# Interconnect.net
KiCad netlist of a schematic drawn in Altium Designer
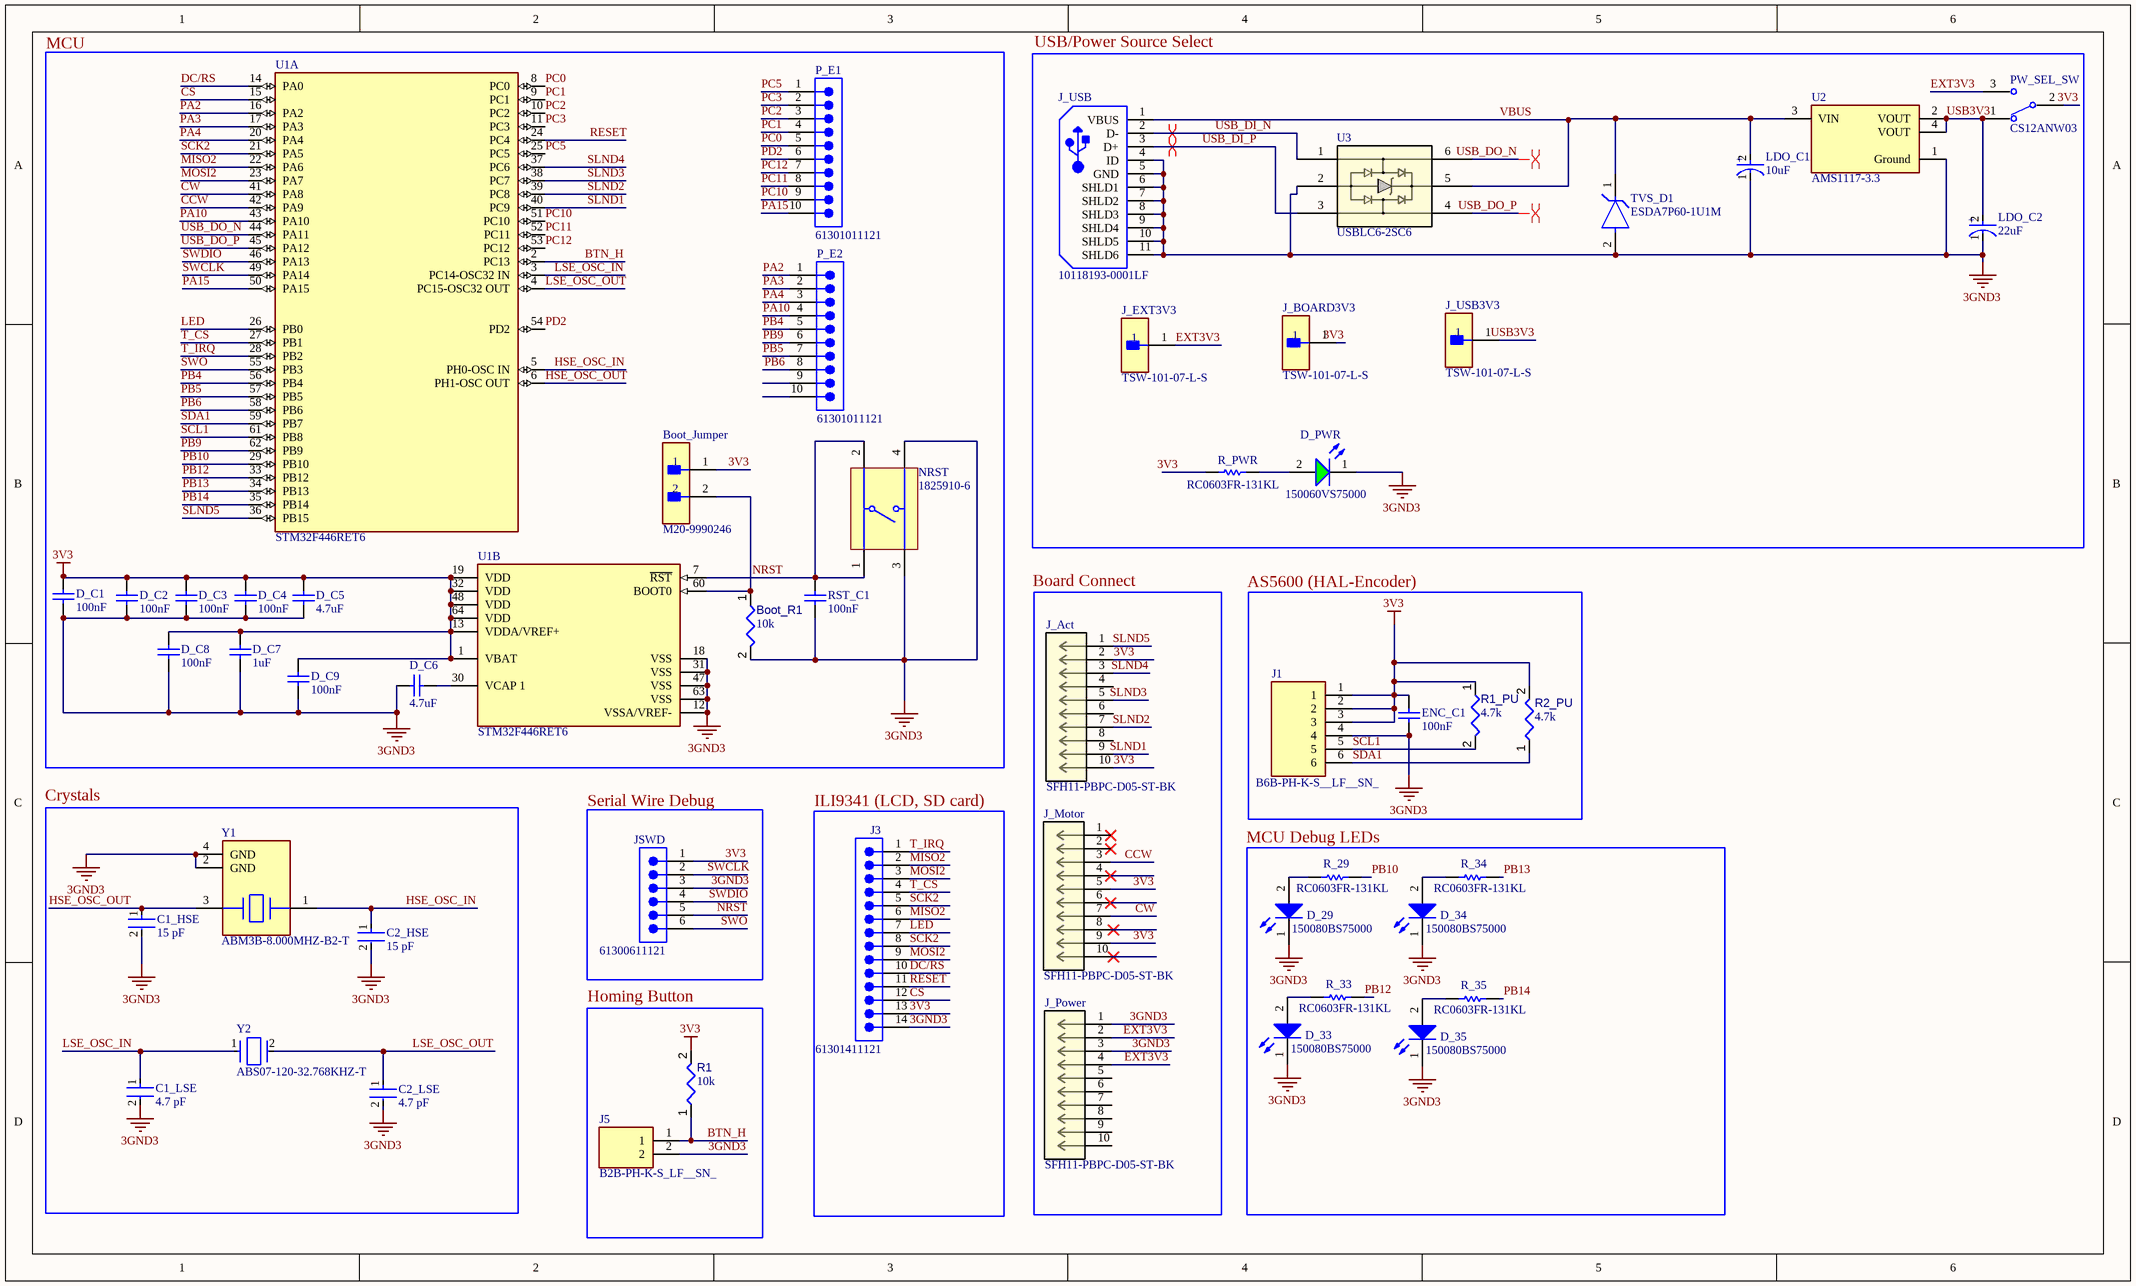
[diagram p0: Interconnect.SchDoc]

(export (version "E")
  (design (tool "Eeschema 10.0.6"))
  (components
    (comp (ref "Boot_Jumper")
      (value "M20-9990246")
      (footprint "FP-M20-9990246-MFG")
      (description "CONN HEADER VERT 2POS 2.54MM")
      (fields
        (field (name "OCTOPART") "https://octopart.com/m20-9990246-harwin-2590635")
        (field (name "MANUFACTURER") "Harwin")
      )
      (libsource (lib "Altium Content Vault") (part "3bc925449376181038e59eaffc5286c"))
    )
    (comp (ref "Boot_R1")
      (value "10k")
      (footprint "RESC1608X55X25ML10T15")
      (description "Chip Resistor, 10 KOhm, +/- 1%, 01 W, -55 to 155 degC, 0603 (1608 Metric)")
      (fields (field (name "POWER") "100mW") (field (name "TOLERANCE") "1%"))
      (libsource (lib "Chathil Rajamanthree") (part "RES-2"))
    )
    (comp (ref "C1_HSE")
      (value "15 pF")
      (footprint "FP-GJM155-0_05-MFG")
      (description "Multi-Layer Ceramic Capacitor 15pF C0G  ±2% 0402 Paper T/R")
      (fields (field (name "TOLERANCE") "2%"))
      (libsource (lib "Altium Content Vault") (part "02cd4be3c70576c341d710602a673aa"))
    )
    (comp (ref "C1_LSE")
      (value "4.7 pF")
      (footprint "FP-GJM155-0_05-MFG")
      (description "Multi-Layer Ceramic Capacitor 15pF C0G  ±2% 0402 Paper T/R")
      (fields (field (name "TOLERANCE") "2%"))
      (libsource (lib "Altium Content Vault") (part "02cd4be3c70576c341d710602a673aa"))
    )
    (comp (ref "C2_HSE")
      (value "15 pF")
      (footprint "FP-GJM155-0_05-MFG")
      (description "Multi-Layer Ceramic Capacitor 15pF C0G  ±2% 0402 Paper T/R")
      (fields (field (name "TOLERANCE") "2%"))
      (libsource (lib "Altium Content Vault") (part "02cd4be3c70576c341d710602a673aa"))
    )
    (comp (ref "C2_LSE")
      (value "4.7 pF")
      (footprint "FP-GJM155-0_05-MFG")
      (description "Multi-Layer Ceramic Capacitor 15pF C0G  ±2% 0402 Paper T/R")
      (fields (field (name "TOLERANCE") "2%"))
      (libsource (lib "Altium Content Vault") (part "02cd4be3c70576c341d710602a673aa"))
    )
    (comp (ref "D_29")
      (value "150080BS75000")
      (footprint "WL-SMCW_0805_150080xx75000")
      (description "Led, Blue, 470 Nm, 3.2 V, 30 Ma, 145 Mcd Rohs Compliant: Yes")
      (libsource (lib "Altium Content Vault") (part "LED_Blue_2A-1K"))
    )
    (comp (ref "D_33")
      (value "150080BS75000")
      (footprint "WL-SMCW_0805_150080xx75000")
      (description "Led, Blue, 470 Nm, 3.2 V, 30 Ma, 145 Mcd Rohs Compliant: Yes")
      (libsource (lib "Altium Content Vault") (part "LED_Blue_2A-1K"))
    )
    (comp (ref "D_34")
      (value "150080BS75000")
      (footprint "WL-SMCW_0805_150080xx75000")
      (description "Led, Blue, 470 Nm, 3.2 V, 30 Ma, 145 Mcd Rohs Compliant: Yes")
      (libsource (lib "Altium Content Vault") (part "LED_Blue_2A-1K"))
    )
    (comp (ref "D_35")
      (value "150080BS75000")
      (footprint "WL-SMCW_0805_150080xx75000")
      (description "Led, Blue, 470 Nm, 3.2 V, 30 Ma, 145 Mcd Rohs Compliant: Yes")
      (libsource (lib "Altium Content Vault") (part "LED_Blue_2A-1K"))
    )
    (comp (ref "D_C1")
      (value "100nF")
      (footprint "CAPC1608X90X35NL15T15")
      (fields (field (name "PART NUMBER") "C0603C104K4RAC7013") (field (name "MANUFACTURER") "Kemet"))
      (libsource (lib "Altium Content Vault") (part "CAP"))
    )
    (comp (ref "D_C2")
      (value "100nF")
      (footprint "CAPC1608X90X35NL15T15")
      (fields (field (name "PART NUMBER") "C0603C104K4RAC7013") (field (name "MANUFACTURER") "Kemet"))
      (libsource (lib "Altium Content Vault") (part "CAP"))
    )
    (comp (ref "D_C3")
      (value "100nF")
      (footprint "CAPC1608X90X35NL15T15")
      (fields (field (name "PART NUMBER") "C0603C104K4RAC7013") (field (name "MANUFACTURER") "Kemet"))
      (libsource (lib "Altium Content Vault") (part "CAP"))
    )
    (comp (ref "D_C4")
      (value "100nF")
      (footprint "CAPC1608X90X35NL15T15")
      (fields (field (name "PART NUMBER") "C0603C104K4RAC7013") (field (name "MANUFACTURER") "Kemet"))
      (libsource (lib "Altium Content Vault") (part "CAP"))
    )
    (comp (ref "D_C5")
      (value "4.7uF")
      (footprint "CAPC1608X90X35NL15T15")
      (fields (field (name "PART NUMBER") "C0603C104K4RAC7013") (field (name "MANUFACTURER") "Kemet"))
      (libsource (lib "Altium Content Vault") (part "CAP"))
    )
    (comp (ref "D_C6")
      (value "4.7uF")
      (footprint "CAPC1608X90X35NL15T15")
      (fields (field (name "PART NUMBER") "C0603C104K4RAC7013") (field (name "MANUFACTURER") "Kemet"))
      (libsource (lib "Altium Content Vault") (part "CAP"))
    )
    (comp (ref "D_C7")
      (value "1uF")
      (footprint "CAPC1608X90X35NL15T15")
      (fields (field (name "PART NUMBER") "C0603C104K4RAC7013") (field (name "MANUFACTURER") "Kemet"))
      (libsource (lib "Altium Content Vault") (part "CAP"))
    )
    (comp (ref "D_C8")
      (value "100nF")
      (footprint "CAPC1608X90X35NL15T15")
      (fields (field (name "PART NUMBER") "C0603C104K4RAC7013") (field (name "MANUFACTURER") "Kemet"))
      (libsource (lib "Altium Content Vault") (part "CAP"))
    )
    (comp (ref "D_C9")
      (value "100nF")
      (footprint "CAPC1608X90X35NL15T15")
      (fields (field (name "PART NUMBER") "C0603C104K4RAC7013") (field (name "MANUFACTURER") "Kemet"))
      (libsource (lib "Altium Content Vault") (part "CAP"))
    )
    (comp (ref "D_PWR")
      (value "150060VS75000")
      (footprint "WL-SMCW_0603_150060xx75000")
      (description "WURTH ELEKTRONIK - 150060VS75000 - LED, Green, SMD, 0603, 30 mA, 2 V, 570 nm")
      (libsource (lib "Altium Content Vault") (part "LED_Green_2A-1K"))
    )
    (comp (ref "ENC_C1")
      (value "100nF")
      (footprint "CAPC1608X90X35NL15T15")
      (fields (field (name "PART NUMBER") "C0603C104K4RAC7013") (field (name "MANUFACTURER") "Kemet"))
      (libsource (lib "Altium Content Vault") (part "CAP"))
    )
    (comp (ref "J1")
      (value "B6B-PH-K-S__LF__SN_")
      (footprint "SamacSys:SHDR6W50P0X200_1X6_1390X450X600P")
      (description "Connector")
      (fields (field (name "MANUFACTURER_PART_NUMBER") "B6B-PH-K-S (LF)(SN)"))
      (libsource (lib "*") (part "B6B-PH-K-S__LF__SN_"))
    )
    (comp (ref "J3")
      (value "61301411121")
      (footprint "61301411121")
      (description "THT Vertical Pin Header WR-PHD, Pitch 2.54 mm, Single Row, 14 pins")
      (libsource (lib "Altium Content Vault") (part "Header_Male_1R_14P"))
    )
    (comp (ref "J5")
      (value "B2B-PH-K-S_LF__SN_")
      (footprint "SamacSys:SHDR2W50P0X200_1X2_590X450X600P")
      (description "Connector")
      (fields
        (field (name "MANUFACTURER_PART_NUMBER") "B2B-PH-K-S(LF)(SN)")
        (field (name "MOUSER PART NUMBER") "306-B2BPHKSLFSNPP")
      )
      (libsource (lib "SamacSys") (part "B2B-PH-K-S_LF__SN_"))
    )
    (comp (ref "JSWD")
      (value "61300611121")
      (footprint "61300611121")
      (description "THT Vertical Pin Header WR-PHD, Pitch 2.54 mm, Single Row, 6 pins")
      (libsource (lib "Altium Content Vault") (part "Header_Male_1R_06P"))
    )
    (comp (ref "J_Act")
      (value "SFH11-PBPC-D05-ST-BK")
      (footprint "CONN_SFH11-xxxC-D05-ST-XX_SUL")
      (description "Description")
      (fields (field (name "COPYRIGHT") "Copyright (C) 2025 Ultra Librarian. All rights reserved."))
      (libsource (lib "SFH11-PBPC-D05-ST-BK") (part "SFH11-PBPC-D05-ST-BK"))
    )
    (comp (ref "J_BOARD3V3")
      (value "TSW-101-07-L-S")
      (footprint "FP-TSW-101-07-L-S-MFG")
      (description "CONN HEADER VERT 1POS")
      (libsource (lib "Altium Content Vault") (part "dd45045ce8184df9e99e12baf3f412c"))
    )
    (comp (ref "J_EXT3V3")
      (value "TSW-101-07-L-S")
      (footprint "FP-TSW-101-07-L-S-MFG")
      (description "CONN HEADER VERT 1POS")
      (libsource (lib "Altium Content Vault") (part "dd45045ce8184df9e99e12baf3f412c"))
    )
    (comp (ref "J_Motor")
      (value "SFH11-PBPC-D05-ST-BK")
      (footprint "CONN_SFH11-xxxC-D05-ST-XX_SUL")
      (description "Description")
      (fields (field (name "COPYRIGHT") "Copyright (C) 2025 Ultra Librarian. All rights reserved."))
      (libsource (lib "SFH11-PBPC-D05-ST-BK") (part "SFH11-PBPC-D05-ST-BK"))
    )
    (comp (ref "J_Power")
      (value "SFH11-PBPC-D05-ST-BK")
      (footprint "CONN_SFH11-xxxC-D05-ST-XX_SUL")
      (description "Description")
      (fields (field (name "COPYRIGHT") "Copyright (C) 2025 Ultra Librarian. All rights reserved."))
      (libsource (lib "SFH11-PBPC-D05-ST-BK") (part "SFH11-PBPC-D05-ST-BK"))
    )
    (comp (ref "J_USB")
      (value "10118193-0001LF")
      (footprint "FCI-10118193-0001LF-5_V")
      (description "Micro USB B Type Receptacle, -55 to 85 degC, 5-Pin SMD, RoHS, Tape and Reel")
      (fields (field (name "MANUFACTURER") "FCI"))
      (libsource (lib "Altium Content Vault") (part "USB-5-6SHLD"))
    )
    (comp (ref "J_USB3V3")
      (value "TSW-101-07-L-S")
      (footprint "FP-TSW-101-07-L-S-MFG")
      (description "CONN HEADER VERT 1POS")
      (libsource (lib "Altium Content Vault") (part "dd45045ce8184df9e99e12baf3f412c"))
    )
    (comp (ref "LDO_C1")
      (value "10uF")
      (footprint "FP-TAJA-MFG")
      (description "10uF 10V  ±20% 3Ω 1206  SMD Tantalum Capacitor")
      (fields (field (name "TOLERANCE") "20%") (field (name "VOLTAGE") "10V"))
      (libsource (lib "Altium Content Vault") (part "203bc49f2ac43e59fd269a8c329ed05"))
    )
    (comp (ref "LDO_C2")
      (value "22uF")
      (footprint "FP-TAJA-MFG")
      (description "10uF 10V  ±20% 3Ω 1206  SMD Tantalum Capacitor")
      (fields (field (name "TOLERANCE") "20%") (field (name "VOLTAGE") "10V"))
      (libsource (lib "Altium Content Vault") (part "203bc49f2ac43e59fd269a8c329ed05"))
    )
    (comp (ref "NRST")
      (value "1825910-6")
      (footprint "TECO-1825910-6_V")
      (description "Tact Switch, SPST-NO, 0.05 A, -35 to 85 degC, 4-Pin THD, RoHS, Bulk")
      (fields (field (name "MANUFACTURER") "TE Connectivity"))
      (libsource (lib "Altium Content Vault") (part "SW-SPST-4_A"))
    )
    (comp (ref "PW_SEL_SW")
      (value "CS12ANW03")
      (footprint "FP-CS12ANW03-MFG")
      (description "SWITCH SLIDE SPDT 3A 125V")
      (libsource (lib "Altium Content Vault") (part "12161840acc88c497b895bf2e19a5b1"))
    )
    (comp (ref "P_E1")
      (value "61301011121")
      (footprint "61301011121")
      (description "THT Vertical Pin Header WR-PHD, Pitch 2.54 mm, Single Row, 10 pins")
      (libsource (lib "Altium Content Vault") (part "Header_Male_1R_10P"))
    )
    (comp (ref "P_E2")
      (value "61301011121")
      (footprint "61301011121")
      (description "THT Vertical Pin Header WR-PHD, Pitch 2.54 mm, Single Row, 10 pins")
      (libsource (lib "Altium Content Vault") (part "Header_Male_1R_10P"))
    )
    (comp (ref "R1")
      (value "10k")
      (footprint "RESC1608X55X25ML10T15")
      (description "Chip Resistor, 10 KOhm, +/- 1%, 01 W, -55 to 155 degC, 0603 (1608 Metric)")
      (fields (field (name "POWER") "100mW") (field (name "TOLERANCE") "1%"))
      (libsource (lib "Chathil Rajamanthree") (part "RES-2"))
    )
    (comp (ref "R1_PU")
      (value "4.7k")
      (footprint "RESC1608X55X25ML10T15")
      (description "Chip Resistor, 10 KOhm, +/- 1%, 01 W, -55 to 155 degC, 0603 (1608 Metric)")
      (fields (field (name "POWER") "100mW") (field (name "TOLERANCE") "1%"))
      (libsource (lib "Chathil Rajamanthree") (part "RES-2"))
    )
    (comp (ref "R2_PU")
      (value "4.7k")
      (footprint "RESC1608X55X25ML10T15")
      (description "Chip Resistor, 10 KOhm, +/- 1%, 01 W, -55 to 155 degC, 0603 (1608 Metric)")
      (fields (field (name "POWER") "100mW") (field (name "TOLERANCE") "1%"))
      (libsource (lib "Chathil Rajamanthree") (part "RES-2"))
    )
    (comp (ref "RST_C1")
      (value "100nF")
      (footprint "CAPC1608X90X35NL15T15")
      (fields (field (name "PART NUMBER") "C0603C104K4RAC7013") (field (name "MANUFACTURER") "Kemet"))
      (libsource (lib "Altium Content Vault") (part "CAP"))
    )
    (comp (ref "R_29")
      (value "RC0603FR-131KL")
      (footprint "RESC1608X55X25NL10T15")
      (fields (field (name "MANUFACTURER") "Yageo"))
      (libsource (lib "Altium Content Vault") (part "RES"))
    )
    (comp (ref "R_33")
      (value "RC0603FR-131KL")
      (footprint "RESC1608X55X25NL10T15")
      (fields (field (name "MANUFACTURER") "Yageo"))
      (libsource (lib "Altium Content Vault") (part "RES"))
    )
    (comp (ref "R_34")
      (value "RC0603FR-131KL")
      (footprint "RESC1608X55X25NL10T15")
      (fields (field (name "MANUFACTURER") "Yageo"))
      (libsource (lib "Altium Content Vault") (part "RES"))
    )
    (comp (ref "R_35")
      (value "RC0603FR-131KL")
      (footprint "RESC1608X55X25NL10T15")
      (fields (field (name "MANUFACTURER") "Yageo"))
      (libsource (lib "Altium Content Vault") (part "RES"))
    )
    (comp (ref "R_PWR")
      (value "RC0603FR-131KL")
      (footprint "RESC1608X55X25NL10T15")
      (fields (field (name "MANUFACTURER") "Yageo"))
      (libsource (lib "Altium Content Vault") (part "RES"))
    )
    (comp (ref "TVS_D1")
      (value "ESDA7P60-1U1M")
      (footprint "FP-1610-MFG")
      (description "TVS DIODE 5V 11.6V 1610")
      (fields
        (field (name "MANUFACTURER") "STMicroelectronics")
        (field (name "OCTOPART") "https://octopart.com/esda7p60-1u1m-stmicroelectronics-52112702")
      )
      (libsource (lib "Altium Content Vault") (part "f813f71cba58e380607f5dd3caf9714"))
    )
    (comp (ref "U1")
      (value "STM32F446RET6")
      (footprint "FP-LQFP64-5W-MFG")
      (description "IC MCU 32BIT 512KB FLASH 64LQFP")
      (fields
        (field (name "OCTOPART") "https://octopart.com/stm32f446ret6-stmicroelectronics-52642920")
        (field (name "MANUFACTURER") "ST")
      )
      (libsource (lib "Altium Content Vault") (part "ee11adc32c0ab33b933cccf4348c338"))
    )
    (comp (ref "U2")
      (value "AMS1117-3.3")
      (footprint "FP-AMS1117-IPC_C")
      (description "LDO Voltage Regulators 1A, 3.3V")
      (fields
        (field (name "OCTOPART") "https://octopart.com/ams1117-3.3-advanced+monolithic+systems-25899300")
        (field (name "MANUFACTURER") "Advanced Monolithic Systems")
      )
      (libsource (lib "Altium Content Vault") (part "8bdbb5f8e77002000e30dd2845d0354"))
    )
    (comp (ref "U3")
      (value "USBLC6-2SC6")
      (footprint "SOT23-6L_STM")
      (description "ESD Protection for USB 2.0 High Speed")
      (fields (field (name "COPYRIGHT") "Copyright (C) 2025 Ultra Librarian. All rights reserved."))
      (libsource (lib "USBLC6-2SC6") (part "USBLC6-2SC6"))
    )
    (comp (ref "Y1")
      (value "ABM3B-8.000MHZ-B2-T")
      (footprint "FP-ABM3B-MFG")
      (description "Crystal 8MHz ±20ppm 18pF SMD-4 5mm x 3.2mm")
      (fields (field (name "TOLERANCE") "20ppm"))
      (libsource (lib "Altium Content Vault") (part "48e526d86b7f2615d98721063c72f49"))
    )
    (comp (ref "Y2")
      (value "ABS07-120-32.768KHZ-T")
      (footprint "FP-ABS07-120-MFG")
      (description "CRYSTAL 32.7680KHZ 6PF SMD")
      (fields (field (name "TOLERANCE") "20ppm"))
      (libsource (lib "Altium Content Vault") (part "c23a69dc6c9e2f18f2079038eb95dd1"))
    )
  )
  (nets
    (net (code "2") (name "/BTN_H") (class "Default")
      (node (ref "J5") (pin "1") (pinfunction "1_1") (pintype "passive"))
      (node (ref "R1") (pin "1") (pinfunction "1_1") (pintype "passive"))
      (node (ref "U1") (pin "2") (pinfunction "PC13_2") (pintype "bidirectional"))
    )
    (net (code "3") (name "/CCW") (class "Default")
      (node (ref "J_Motor") (pin "3") (pinfunction "3_3") (pintype "passive"))
      (node (ref "U1") (pin "42") (pinfunction "PA9_42") (pintype "bidirectional"))
    )
    (net (code "4") (name "/CS") (class "Default")
      (node (ref "J3") (pin "12") (pinfunction "12_12") (pintype "passive"))
      (node (ref "U1") (pin "15") (pinfunction "PA1_15") (pintype "bidirectional"))
    )
    (net (code "5") (name "/CW") (class "Default")
      (node (ref "J_Motor") (pin "7") (pinfunction "7_7") (pintype "passive"))
      (node (ref "U1") (pin "41") (pinfunction "PA8_41") (pintype "bidirectional"))
    )
    (net (code "6") (name "/DC{slash}RS") (class "Default")
      (node (ref "J3") (pin "10") (pinfunction "10_10") (pintype "passive"))
      (node (ref "U1") (pin "14") (pinfunction "PA0_14") (pintype "bidirectional"))
    )
    (net (code "7") (name "/EXT3V3") (class "Default")
      (node (ref "J_EXT3V3") (pin "1") (pinfunction "1_1") (pintype "passive"))
      (node (ref "J_Power") (pin "2") (pinfunction "2_2") (pintype "passive"))
      (node (ref "J_Power") (pin "4") (pinfunction "4_4") (pintype "passive"))
      (node (ref "PW_SEL_SW") (pin "3") (pinfunction "3_3") (pintype "passive"))
    )
    (net (code "8") (name "/HSE_OSC_IN") (class "Default")
      (node (ref "C2_HSE") (pin "1") (pinfunction "1_1") (pintype "passive"))
      (node (ref "U1") (pin "5") (pinfunction "PH0-OSC_IN_5") (pintype "bidirectional"))
      (node (ref "Y1") (pin "1") (pinfunction "1_1") (pintype "passive"))
    )
    (net (code "9") (name "/HSE_OSC_OUT") (class "Default")
      (node (ref "C1_HSE") (pin "1") (pinfunction "1_1") (pintype "passive"))
      (node (ref "U1") (pin "6") (pinfunction "PH1-OSC_OUT_6") (pintype "bidirectional"))
      (node (ref "Y1") (pin "3") (pinfunction "3_3") (pintype "passive"))
    )
    (net (code "10") (name "/LED") (class "Default")
      (node (ref "J3") (pin "7") (pinfunction "7_7") (pintype "passive"))
      (node (ref "U1") (pin "26") (pinfunction "PB0_26") (pintype "bidirectional"))
    )
    (net (code "11") (name "/LSE_OSC_IN") (class "Default")
      (node (ref "C1_LSE") (pin "1") (pinfunction "1_1") (pintype "passive"))
      (node (ref "U1") (pin "3") (pinfunction "PC14-OSC32_IN_3") (pintype "bidirectional"))
      (node (ref "Y2") (pin "1") (pinfunction "1_1") (pintype "passive"))
    )
    (net (code "12") (name "/LSE_OSC_OUT") (class "Default")
      (node (ref "C2_LSE") (pin "1") (pinfunction "1_1") (pintype "passive"))
      (node (ref "U1") (pin "4") (pinfunction "PC15-OSC32_OUT_4") (pintype "bidirectional"))
      (node (ref "Y2") (pin "2") (pinfunction "2_2") (pintype "passive"))
    )
    (net (code "13") (name "/MISO2") (class "Default")
      (node (ref "J3") (pin "2") (pinfunction "2_2") (pintype "passive"))
      (node (ref "J3") (pin "6") (pinfunction "6_6") (pintype "passive"))
      (node (ref "U1") (pin "22") (pinfunction "PA6_22") (pintype "bidirectional"))
    )
    (net (code "14") (name "/MOSI2") (class "Default")
      (node (ref "J3") (pin "3") (pinfunction "3_3") (pintype "passive"))
      (node (ref "J3") (pin "9") (pinfunction "9_9") (pintype "passive"))
      (node (ref "U1") (pin "23") (pinfunction "PA7_23") (pintype "bidirectional"))
    )
    (net (code "15") (name "/NRST") (class "Default")
      (node (ref "JSWD") (pin "5") (pinfunction "5_5") (pintype "passive"))
      (node (ref "NRST") (pin "1") (pinfunction "1_1") (pintype "passive"))
      (node (ref "NRST") (pin "2") (pinfunction "2_2") (pintype "passive"))
      (node (ref "RST_C1") (pin "1") (pinfunction "1_1") (pintype "passive"))
      (node (ref "U1") (pin "7") (pinfunction "~{RST}_7") (pintype "input"))
    )
    (net (code "16") (name "/PA2") (class "Default")
      (node (ref "P_E2") (pin "1") (pinfunction "1_1") (pintype "passive"))
      (node (ref "U1") (pin "16") (pinfunction "PA2_16") (pintype "bidirectional"))
    )
    (net (code "17") (name "/PA3") (class "Default")
      (node (ref "P_E2") (pin "2") (pinfunction "2_2") (pintype "passive"))
      (node (ref "U1") (pin "17") (pinfunction "PA3_17") (pintype "bidirectional"))
    )
    (net (code "18") (name "/PA4") (class "Default")
      (node (ref "P_E2") (pin "3") (pinfunction "3_3") (pintype "passive"))
      (node (ref "U1") (pin "20") (pinfunction "PA4_20") (pintype "bidirectional"))
    )
    (net (code "19") (name "/PA10") (class "Default")
      (node (ref "P_E2") (pin "4") (pinfunction "4_4") (pintype "passive"))
      (node (ref "U1") (pin "43") (pinfunction "PA10_43") (pintype "bidirectional"))
    )
    (net (code "20") (name "/PA15") (class "Default")
      (node (ref "P_E1") (pin "10") (pinfunction "10_10") (pintype "passive"))
      (node (ref "U1") (pin "50") (pinfunction "PA15_50") (pintype "bidirectional"))
    )
    (net (code "21") (name "/PB4") (class "Default")
      (node (ref "P_E2") (pin "5") (pinfunction "5_5") (pintype "passive"))
      (node (ref "U1") (pin "56") (pinfunction "PB4_56") (pintype "bidirectional"))
    )
    (net (code "22") (name "/PB5") (class "Default")
      (node (ref "P_E2") (pin "7") (pinfunction "7_7") (pintype "passive"))
      (node (ref "U1") (pin "57") (pinfunction "PB5_57") (pintype "bidirectional"))
    )
    (net (code "23") (name "/PB6") (class "Default")
      (node (ref "P_E2") (pin "8") (pinfunction "8_8") (pintype "passive"))
      (node (ref "U1") (pin "58") (pinfunction "PB6_58") (pintype "bidirectional"))
    )
    (net (code "24") (name "/PB9") (class "Default")
      (node (ref "P_E2") (pin "6") (pinfunction "6_6") (pintype "passive"))
      (node (ref "U1") (pin "62") (pinfunction "PB9_62") (pintype "bidirectional"))
    )
    (net (code "25") (name "/PB10") (class "Default")
      (node (ref "R_29") (pin "2") (pinfunction "2_2") (pintype "passive"))
      (node (ref "U1") (pin "29") (pinfunction "PB10_29") (pintype "bidirectional"))
    )
    (net (code "26") (name "/PB12") (class "Default")
      (node (ref "R_33") (pin "2") (pinfunction "2_2") (pintype "passive"))
      (node (ref "U1") (pin "33") (pinfunction "PB12_33") (pintype "bidirectional"))
    )
    (net (code "27") (name "/PB13") (class "Default")
      (node (ref "R_34") (pin "2") (pinfunction "2_2") (pintype "passive"))
      (node (ref "U1") (pin "34") (pinfunction "PB13_34") (pintype "bidirectional"))
    )
    (net (code "28") (name "/PB14") (class "Default")
      (node (ref "R_35") (pin "2") (pinfunction "2_2") (pintype "passive"))
      (node (ref "U1") (pin "35") (pinfunction "PB14_35") (pintype "bidirectional"))
    )
    (net (code "29") (name "/PC0") (class "Default")
      (node (ref "P_E1") (pin "5") (pinfunction "5_5") (pintype "passive"))
      (node (ref "U1") (pin "8") (pinfunction "PC0_8") (pintype "bidirectional"))
    )
    (net (code "30") (name "/PC1") (class "Default")
      (node (ref "P_E1") (pin "4") (pinfunction "4_4") (pintype "passive"))
      (node (ref "U1") (pin "9") (pinfunction "PC1_9") (pintype "bidirectional"))
    )
    (net (code "31") (name "/PC2") (class "Default")
      (node (ref "P_E1") (pin "3") (pinfunction "3_3") (pintype "passive"))
      (node (ref "U1") (pin "10") (pinfunction "PC2_10") (pintype "bidirectional"))
    )
    (net (code "32") (name "/PC3") (class "Default")
      (node (ref "P_E1") (pin "2") (pinfunction "2_2") (pintype "passive"))
      (node (ref "U1") (pin "11") (pinfunction "PC3_11") (pintype "bidirectional"))
    )
    (net (code "33") (name "/PC5") (class "Default")
      (node (ref "P_E1") (pin "1") (pinfunction "1_1") (pintype "passive"))
      (node (ref "U1") (pin "25") (pinfunction "PC5_25") (pintype "bidirectional"))
    )
    (net (code "34") (name "/PC10") (class "Default")
      (node (ref "P_E1") (pin "9") (pinfunction "9_9") (pintype "passive"))
      (node (ref "U1") (pin "51") (pinfunction "PC10_51") (pintype "bidirectional"))
    )
    (net (code "35") (name "/PC11") (class "Default")
      (node (ref "P_E1") (pin "8") (pinfunction "8_8") (pintype "passive"))
      (node (ref "U1") (pin "52") (pinfunction "PC11_52") (pintype "bidirectional"))
    )
    (net (code "36") (name "/PC12") (class "Default")
      (node (ref "P_E1") (pin "7") (pinfunction "7_7") (pintype "passive"))
      (node (ref "U1") (pin "53") (pinfunction "PC12_53") (pintype "bidirectional"))
    )
    (net (code "37") (name "/PD2") (class "Default")
      (node (ref "P_E1") (pin "6") (pinfunction "6_6") (pintype "passive"))
      (node (ref "U1") (pin "54") (pinfunction "PD2_54") (pintype "bidirectional"))
    )
    (net (code "38") (name "/RESET") (class "Default")
      (node (ref "J3") (pin "11") (pinfunction "11_11") (pintype "passive"))
      (node (ref "U1") (pin "24") (pinfunction "PC4_24") (pintype "bidirectional"))
    )
    (net (code "39") (name "/SCK2") (class "Default")
      (node (ref "J3") (pin "5") (pinfunction "5_5") (pintype "passive"))
      (node (ref "J3") (pin "8") (pinfunction "8_8") (pintype "passive"))
      (node (ref "U1") (pin "21") (pinfunction "PA5_21") (pintype "bidirectional"))
    )
    (net (code "40") (name "/SCL1") (class "Default")
      (node (ref "J1") (pin "5") (pinfunction "5_5") (pintype "passive"))
      (node (ref "R1_PU") (pin "2") (pinfunction "2_2") (pintype "passive"))
      (node (ref "U1") (pin "61") (pinfunction "PB8_61") (pintype "bidirectional"))
    )
    (net (code "41") (name "/SDA1") (class "Default")
      (node (ref "J1") (pin "6") (pinfunction "6_6") (pintype "passive"))
      (node (ref "R2_PU") (pin "1") (pinfunction "1_1") (pintype "passive"))
      (node (ref "U1") (pin "59") (pinfunction "PB7_59") (pintype "bidirectional"))
    )
    (net (code "42") (name "/SLND1") (class "Default")
      (node (ref "J_Act") (pin "9") (pinfunction "9_9") (pintype "passive"))
      (node (ref "U1") (pin "40") (pinfunction "PC9_40") (pintype "bidirectional"))
    )
    (net (code "43") (name "/SLND2") (class "Default")
      (node (ref "J_Act") (pin "7") (pinfunction "7_7") (pintype "passive"))
      (node (ref "U1") (pin "39") (pinfunction "PC8_39") (pintype "bidirectional"))
    )
    (net (code "44") (name "/SLND3") (class "Default")
      (node (ref "J_Act") (pin "5") (pinfunction "5_5") (pintype "passive"))
      (node (ref "U1") (pin "38") (pinfunction "PC7_38") (pintype "bidirectional"))
    )
    (net (code "45") (name "/SLND4") (class "Default")
      (node (ref "J_Act") (pin "3") (pinfunction "3_3") (pintype "passive"))
      (node (ref "U1") (pin "37") (pinfunction "PC6_37") (pintype "bidirectional"))
    )
    (net (code "46") (name "/SLND5") (class "Default")
      (node (ref "J_Act") (pin "1") (pinfunction "1_1") (pintype "passive"))
      (node (ref "U1") (pin "36") (pinfunction "PB15_36") (pintype "bidirectional"))
    )
    (net (code "47") (name "/SWCLK") (class "Default")
      (node (ref "JSWD") (pin "2") (pinfunction "2_2") (pintype "passive"))
      (node (ref "U1") (pin "49") (pinfunction "PA14_49") (pintype "bidirectional"))
    )
    (net (code "48") (name "/SWDIO") (class "Default")
      (node (ref "JSWD") (pin "4") (pinfunction "4_4") (pintype "passive"))
      (node (ref "U1") (pin "46") (pinfunction "PA13_46") (pintype "bidirectional"))
    )
    (net (code "49") (name "/SWO") (class "Default")
      (node (ref "JSWD") (pin "6") (pinfunction "6_6") (pintype "passive"))
      (node (ref "U1") (pin "55") (pinfunction "PB3_55") (pintype "bidirectional"))
    )
    (net (code "50") (name "/T_CS") (class "Default")
      (node (ref "J3") (pin "4") (pinfunction "4_4") (pintype "passive"))
      (node (ref "U1") (pin "27") (pinfunction "PB1_27") (pintype "bidirectional"))
    )
    (net (code "51") (name "/T_IRQ") (class "Default")
      (node (ref "J3") (pin "1") (pinfunction "1_1") (pintype "passive"))
      (node (ref "U1") (pin "28") (pinfunction "PB2_28") (pintype "bidirectional"))
    )
    (net (code "52") (name "/USB3V3") (class "Default")
      (node (ref "J_USB3V3") (pin "1") (pinfunction "1_1") (pintype "passive"))
      (node (ref "LDO_C2") (pin "2") (pinfunction "A_2") (pintype "passive"))
      (node (ref "PW_SEL_SW") (pin "1") (pinfunction "1_1") (pintype "passive"))
      (node (ref "U2") (pin "2") (pinfunction "VOUT_2") (pintype "passive"))
      (node (ref "U2") (pin "4") (pinfunction "VOUT_4") (pintype "passive"))
    )
    (net (code "53") (name "/USB_DI_N") (class "Default")
      (node (ref "J_USB") (pin "2") (pinfunction "D-_2") (pintype "passive"))
      (node (ref "U3") (pin "1") (pinfunction "1_1") (pintype "passive"))
    )
    (net (code "54") (name "/USB_DI_P") (class "Default")
      (node (ref "J_USB") (pin "3") (pinfunction "D+_3") (pintype "passive"))
      (node (ref "U3") (pin "3") (pinfunction "3_3") (pintype "passive"))
    )
    (net (code "55") (name "/USB_DO_N") (class "Default")
      (node (ref "U1") (pin "44") (pinfunction "PA11_44") (pintype "bidirectional"))
      (node (ref "U3") (pin "6") (pinfunction "6_6") (pintype "passive"))
    )
    (net (code "56") (name "/USB_DO_P") (class "Default")
      (node (ref "U1") (pin "45") (pinfunction "PA12_45") (pintype "bidirectional"))
      (node (ref "U3") (pin "4") (pinfunction "4_4") (pintype "passive"))
    )
    (net (code "57") (name "/VBUS") (class "Default")
      (node (ref "J_USB") (pin "1") (pinfunction "VBUS_1") (pintype "passive"))
      (node (ref "LDO_C1") (pin "2") (pinfunction "A_2") (pintype "passive"))
      (node (ref "TVS_D1") (pin "1") (pinfunction "C_1") (pintype "passive"))
      (node (ref "U2") (pin "3") (pinfunction "VIN_3") (pintype "power_in"))
      (node (ref "U3") (pin "5") (pinfunction "5_5") (pintype "passive"))
    )
    (net (code "58") (name "3GND3") (class "Default")
      (node (ref "Boot_R1") (pin "2") (pinfunction "2_2") (pintype "passive"))
      (node (ref "C1_HSE") (pin "2") (pinfunction "2_2") (pintype "passive"))
      (node (ref "C1_LSE") (pin "2") (pinfunction "2_2") (pintype "passive"))
      (node (ref "C2_HSE") (pin "2") (pinfunction "2_2") (pintype "passive"))
      (node (ref "C2_LSE") (pin "2") (pinfunction "2_2") (pintype "passive"))
      (node (ref "D_29") (pin "1") (pinfunction "K_1") (pintype "passive"))
      (node (ref "D_33") (pin "1") (pinfunction "K_1") (pintype "passive"))
      (node (ref "D_34") (pin "1") (pinfunction "K_1") (pintype "passive"))
      (node (ref "D_35") (pin "1") (pinfunction "K_1") (pintype "passive"))
      (node (ref "D_C1") (pin "2") (pinfunction "2_2") (pintype "passive"))
      (node (ref "D_C2") (pin "2") (pinfunction "2_2") (pintype "passive"))
      (node (ref "D_C3") (pin "2") (pinfunction "2_2") (pintype "passive"))
      (node (ref "D_C4") (pin "1") (pinfunction "1_1") (pintype "passive"))
      (node (ref "D_C5") (pin "2") (pinfunction "2_2") (pintype "passive"))
      (node (ref "D_C6") (pin "2") (pinfunction "2_2") (pintype "passive"))
      (node (ref "D_C7") (pin "1") (pinfunction "1_1") (pintype "passive"))
      (node (ref "D_C8") (pin "1") (pinfunction "1_1") (pintype "passive"))
      (node (ref "D_C9") (pin "2") (pinfunction "2_2") (pintype "passive"))
      (node (ref "D_PWR") (pin "1") (pinfunction "K_1") (pintype "passive"))
      (node (ref "ENC_C1") (pin "1") (pinfunction "1_1") (pintype "passive"))
      (node (ref "J1") (pin "4") (pinfunction "4_4") (pintype "passive"))
      (node (ref "J3") (pin "14") (pinfunction "14_14") (pintype "passive"))
      (node (ref "J5") (pin "2") (pinfunction "2_2") (pintype "passive"))
      (node (ref "JSWD") (pin "3") (pinfunction "3_3") (pintype "passive"))
      (node (ref "J_Power") (pin "1") (pinfunction "1_1") (pintype "passive"))
      (node (ref "J_Power") (pin "3") (pinfunction "3_3") (pintype "passive"))
      (node (ref "J_USB") (pin "10") (pinfunction "SHLD5_10") (pintype "passive"))
      (node (ref "J_USB") (pin "11") (pinfunction "SHLD6_11") (pintype "passive"))
      (node (ref "J_USB") (pin "4") (pinfunction "ID_4") (pintype "passive"))
      (node (ref "J_USB") (pin "5") (pinfunction "GND_5") (pintype "passive"))
      (node (ref "J_USB") (pin "6") (pinfunction "SHLD1_6") (pintype "passive"))
      (node (ref "J_USB") (pin "7") (pinfunction "SHLD2_7") (pintype "passive"))
      (node (ref "J_USB") (pin "8") (pinfunction "SHLD3_8") (pintype "passive"))
      (node (ref "J_USB") (pin "9") (pinfunction "SHLD4_9") (pintype "passive"))
      (node (ref "LDO_C1") (pin "1") (pinfunction "C_1") (pintype "passive"))
      (node (ref "LDO_C2") (pin "1") (pinfunction "C_1") (pintype "passive"))
      (node (ref "NRST") (pin "3") (pinfunction "3_3") (pintype "passive"))
      (node (ref "NRST") (pin "4") (pinfunction "4_4") (pintype "passive"))
      (node (ref "RST_C1") (pin "2") (pinfunction "2_2") (pintype "passive"))
      (node (ref "TVS_D1") (pin "2") (pinfunction "A_2") (pintype "passive"))
      (node (ref "U1") (pin "12") (pinfunction "VSSA/VREF-_12") (pintype "power_in"))
      (node (ref "U1") (pin "18") (pinfunction "VSS_18") (pintype "power_in"))
      (node (ref "U1") (pin "31") (pinfunction "VSS_31") (pintype "power_in"))
      (node (ref "U1") (pin "47") (pinfunction "VSS_47") (pintype "power_in"))
      (node (ref "U1") (pin "63") (pinfunction "VSS_63") (pintype "power_in"))
      (node (ref "U2") (pin "1") (pinfunction "Ground_1") (pintype "power_in"))
      (node (ref "U3") (pin "2") (pinfunction "2_2") (pintype "passive"))
      (node (ref "Y1") (pin "2") (pinfunction "GND_2") (pintype "power_in"))
      (node (ref "Y1") (pin "4") (pinfunction "GND_4") (pintype "power_in"))
    )
    (net (code "59") (name "3V3") (class "Default")
      (node (ref "Boot_Jumper") (pin "1") (pinfunction "1_1") (pintype "passive"))
      (node (ref "D_C1") (pin "1") (pinfunction "1_1") (pintype "passive"))
      (node (ref "D_C2") (pin "1") (pinfunction "1_1") (pintype "passive"))
      (node (ref "D_C3") (pin "1") (pinfunction "1_1") (pintype "passive"))
      (node (ref "D_C4") (pin "2") (pinfunction "2_2") (pintype "passive"))
      (node (ref "D_C5") (pin "1") (pinfunction "1_1") (pintype "passive"))
      (node (ref "D_C7") (pin "2") (pinfunction "2_2") (pintype "passive"))
      (node (ref "D_C8") (pin "2") (pinfunction "2_2") (pintype "passive"))
      (node (ref "D_C9") (pin "1") (pinfunction "1_1") (pintype "passive"))
      (node (ref "ENC_C1") (pin "2") (pinfunction "2_2") (pintype "passive"))
      (node (ref "J1") (pin "1") (pinfunction "1_1") (pintype "passive"))
      (node (ref "J1") (pin "2") (pinfunction "2_2") (pintype "passive"))
      (node (ref "J1") (pin "3") (pinfunction "3_3") (pintype "passive"))
      (node (ref "J3") (pin "13") (pinfunction "13_13") (pintype "passive"))
      (node (ref "JSWD") (pin "1") (pinfunction "1_1") (pintype "passive"))
      (node (ref "J_Act") (pin "10") (pinfunction "10_10") (pintype "passive"))
      (node (ref "J_Act") (pin "2") (pinfunction "2_2") (pintype "passive"))
      (node (ref "J_BOARD3V3") (pin "1") (pinfunction "1_1") (pintype "passive"))
      (node (ref "J_Motor") (pin "5") (pinfunction "5_5") (pintype "passive"))
      (node (ref "J_Motor") (pin "9") (pinfunction "9_9") (pintype "passive"))
      (node (ref "PW_SEL_SW") (pin "2") (pinfunction "2(COM)_2") (pintype "passive"))
      (node (ref "R1") (pin "2") (pinfunction "2_2") (pintype "passive"))
      (node (ref "R1_PU") (pin "1") (pinfunction "1_1") (pintype "passive"))
      (node (ref "R2_PU") (pin "2") (pinfunction "2_2") (pintype "passive"))
      (node (ref "R_PWR") (pin "1") (pinfunction "1_1") (pintype "passive"))
      (node (ref "U1") (pin "1") (pinfunction "VBAT_1") (pintype "power_in"))
      (node (ref "U1") (pin "13") (pinfunction "VDDA/VREF+_13") (pintype "power_in"))
      (node (ref "U1") (pin "19") (pinfunction "VDD_19") (pintype "power_in"))
      (node (ref "U1") (pin "32") (pinfunction "VDD_32") (pintype "power_in"))
      (node (ref "U1") (pin "48") (pinfunction "VDD_48") (pintype "power_in"))
      (node (ref "U1") (pin "64") (pinfunction "VDD_64") (pintype "power_in"))
    )
    (net (code "60") (name "Net-(D_29-A)") (class "Default")
      (node (ref "D_29") (pin "2") (pinfunction "A_2") (pintype "passive"))
      (node (ref "R_29") (pin "1") (pinfunction "1_1") (pintype "passive"))
    )
    (net (code "61") (name "Net-(D_33-A)") (class "Default")
      (node (ref "D_33") (pin "2") (pinfunction "A_2") (pintype "passive"))
      (node (ref "R_33") (pin "1") (pinfunction "1_1") (pintype "passive"))
    )
    (net (code "62") (name "Net-(D_34-A)") (class "Default")
      (node (ref "D_34") (pin "2") (pinfunction "A_2") (pintype "passive"))
      (node (ref "R_34") (pin "1") (pinfunction "1_1") (pintype "passive"))
    )
    (net (code "63") (name "Net-(D_35-A)") (class "Default")
      (node (ref "D_35") (pin "2") (pinfunction "A_2") (pintype "passive"))
      (node (ref "R_35") (pin "1") (pinfunction "1_1") (pintype "passive"))
    )
    (net (code "64") (name "Net-(D_PWR-A)") (class "Default")
      (node (ref "D_PWR") (pin "2") (pinfunction "A_2") (pintype "passive"))
      (node (ref "R_PWR") (pin "2") (pinfunction "2_2") (pintype "passive"))
    )
    (net (code "65") (name "Net-(U1B-BOOT0)") (class "Default")
      (node (ref "Boot_Jumper") (pin "2") (pinfunction "2_2") (pintype "passive"))
      (node (ref "Boot_R1") (pin "1") (pinfunction "1_1") (pintype "passive"))
      (node (ref "U1") (pin "60") (pinfunction "BOOT0_60") (pintype "input"))
    )
    (net (code "66") (name "Net-(U1B-VCAP_1)") (class "Default")
      (node (ref "D_C6") (pin "1") (pinfunction "1_1") (pintype "passive"))
      (node (ref "U1") (pin "30") (pinfunction "VCAP_1_30") (pintype "power_in"))
    )
    (net (code "67") (name "unconnected-(J_Act-Pad4)") (class "Default")
      (node (ref "J_Act") (pin "4") (pinfunction "4_4") (pintype "passive"))
    )
    (net (code "68") (name "unconnected-(J_Act-Pad6)") (class "Default")
      (node (ref "J_Act") (pin "6") (pinfunction "6_6") (pintype "passive"))
    )
    (net (code "69") (name "unconnected-(J_Act-Pad8)") (class "Default")
      (node (ref "J_Act") (pin "8") (pinfunction "8_8") (pintype "passive"))
    )
    (net (code "70") (name "unconnected-(J_Motor-Pad1)") (class "Default")
      (node (ref "J_Motor") (pin "1") (pinfunction "1_1") (pintype "passive+no_connect"))
    )
    (net (code "71") (name "unconnected-(J_Motor-Pad2)") (class "Default")
      (node (ref "J_Motor") (pin "2") (pinfunction "2_2") (pintype "passive+no_connect"))
    )
    (net (code "72") (name "unconnected-(J_Motor-Pad4)") (class "Default")
      (node (ref "J_Motor") (pin "4") (pinfunction "4_4") (pintype "passive+no_connect"))
    )
    (net (code "73") (name "unconnected-(J_Motor-Pad6)") (class "Default")
      (node (ref "J_Motor") (pin "6") (pinfunction "6_6") (pintype "passive+no_connect"))
    )
    (net (code "74") (name "unconnected-(J_Motor-Pad8)") (class "Default")
      (node (ref "J_Motor") (pin "8") (pinfunction "8_8") (pintype "passive"))
    )
    (net (code "75") (name "unconnected-(J_Motor-Pad10)") (class "Default")
      (node (ref "J_Motor") (pin "10") (pinfunction "10_10") (pintype "passive"))
    )
    (net (code "76") (name "unconnected-(J_Power-Pad5)") (class "Default")
      (node (ref "J_Power") (pin "5") (pinfunction "5_5") (pintype "passive"))
    )
    (net (code "77") (name "unconnected-(J_Power-Pad6)") (class "Default")
      (node (ref "J_Power") (pin "6") (pinfunction "6_6") (pintype "passive"))
    )
    (net (code "78") (name "unconnected-(J_Power-Pad7)") (class "Default")
      (node (ref "J_Power") (pin "7") (pinfunction "7_7") (pintype "passive"))
    )
    (net (code "79") (name "unconnected-(J_Power-Pad8)") (class "Default")
      (node (ref "J_Power") (pin "8") (pinfunction "8_8") (pintype "passive"))
    )
    (net (code "80") (name "unconnected-(J_Power-Pad9)") (class "Default")
      (node (ref "J_Power") (pin "9") (pinfunction "9_9") (pintype "passive"))
    )
    (net (code "81") (name "unconnected-(J_Power-Pad10)") (class "Default")
      (node (ref "J_Power") (pin "10") (pinfunction "10_10") (pintype "passive"))
    )
    (net (code "82") (name "unconnected-(P_E2-Pad9)") (class "Default")
      (node (ref "P_E2") (pin "9") (pinfunction "9_9") (pintype "passive"))
    )
    (net (code "83") (name "unconnected-(P_E2-Pad10)") (class "Default")
      (node (ref "P_E2") (pin "10") (pinfunction "10_10") (pintype "passive"))
    )
  )
)
